# tractor.net
KiCad netlist of a schematic drawn in EAGLE
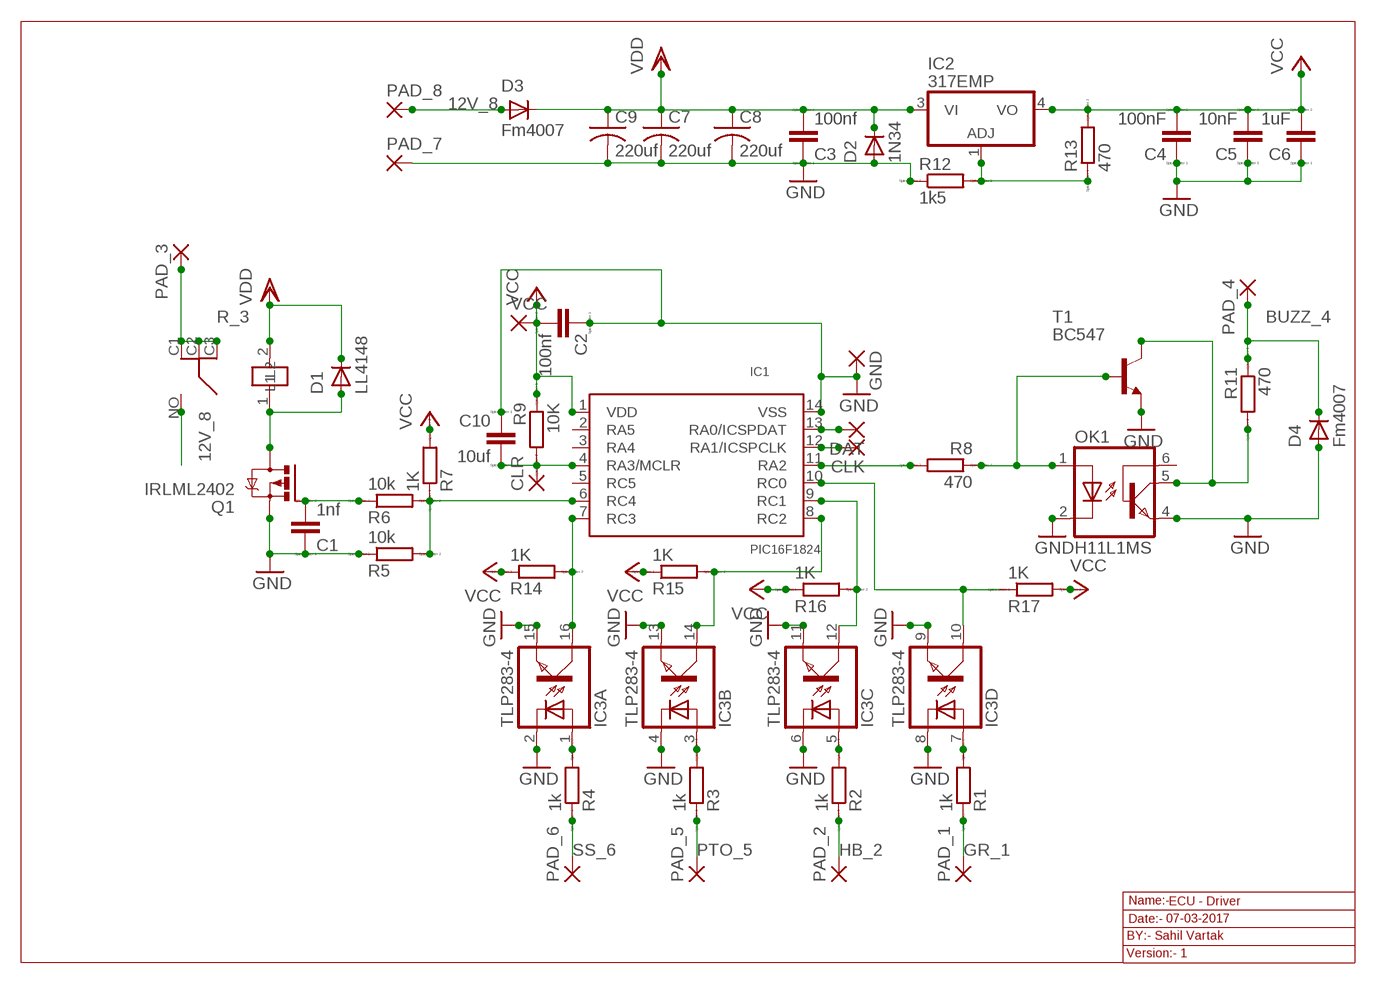
[diagram p0: schematic, sheet 1]

(export (version "E")
  (design (tool "Eeschema 10.0.6"))
  (components
    (comp (ref "C1")
      (value "1nf")
      (footprint "eagle-import:C0603")
      (libsource (lib "eagle-import") (part "CC0603"))
    )
    (comp (ref "C2")
      (value "100nf")
      (footprint "eagle-import:C0603")
      (libsource (lib "eagle-import") (part "CC0603"))
    )
    (comp (ref "C3")
      (value "100nf")
      (footprint "eagle-import:C0603")
      (libsource (lib "eagle-import") (part "CC0603"))
    )
    (comp (ref "C4")
      (value "100nF")
      (footprint "eagle-import:C0603")
      (libsource (lib "eagle-import") (part "CC0603"))
    )
    (comp (ref "C5")
      (value "10nF")
      (footprint "eagle-import:C0603")
      (libsource (lib "eagle-import") (part "CC0603"))
    )
    (comp (ref "C6")
      (value "1uF")
      (footprint "eagle-import:C0603")
      (libsource (lib "eagle-import") (part "CC0603"))
    )
    (comp (ref "C7")
      (value "220uf")
      (footprint "eagle-import:C025-025X050")
      (libsource (lib "eagle-import") (part "C-US025-025X050"))
    )
    (comp (ref "C8")
      (value "220uf")
      (footprint "eagle-import:C025-025X050")
      (libsource (lib "eagle-import") (part "C-US025-025X050"))
    )
    (comp (ref "C9")
      (value "220uf")
      (footprint "eagle-import:C025-025X050")
      (libsource (lib "eagle-import") (part "C-US025-025X050"))
    )
    (comp (ref "C10")
      (value "10uf")
      (footprint "eagle-import:C0603")
      (libsource (lib "eagle-import") (part "CC0603"))
    )
    (comp (ref "CLK")
      (value "1,6/0,8")
      (footprint "eagle-import:1,6_0,8")
      (libsource (lib "eagle-import") (part "1,6/0,8"))
    )
    (comp (ref "CLR")
      (value "1,6/0,8")
      (footprint "eagle-import:1,6_0,8")
      (libsource (lib "eagle-import") (part "1,6/0,8"))
    )
    (comp (ref "D1")
      (value "LL4148")
      (footprint "eagle-import:SMA-DO214AC")
      (libsource (lib "eagle-import") (part "GF1"))
    )
    (comp (ref "D2")
      (value "1N34")
      (footprint "eagle-import:SMA-DO214AC")
      (libsource (lib "eagle-import") (part "GF1"))
    )
    (comp (ref "D3")
      (value "Fm4007")
      (footprint "eagle-import:SMA-DO214AC")
      (libsource (lib "eagle-import") (part "GF1"))
    )
    (comp (ref "D4")
      (value "Fm4007")
      (footprint "eagle-import:SMA-DO214AC")
      (libsource (lib "eagle-import") (part "GF1"))
    )
    (comp (ref "DAT")
      (value "1,6/0,8")
      (footprint "eagle-import:1,6_0,8")
      (libsource (lib "eagle-import") (part "1,6/0,8"))
    )
    (comp (ref "GND")
      (value "1,6/0,8")
      (footprint "eagle-import:1,6_0,8")
      (libsource (lib "eagle-import") (part "1,6/0,8"))
    )
    (comp (ref "IC1")
      (value "PIC16F1824")
      (footprint "eagle-import:SO-14")
      (libsource (lib "eagle-import") (part "PIC16F1824"))
    )
    (comp (ref "IC2")
      (value "317EMP")
      (footprint "eagle-import:SOT223")
      (libsource (lib "eagle-import") (part "317EMP"))
    )
    (comp (ref "IC3")
      (value "TLP283-4")
      (footprint "eagle-import:MINI-FLAT-16")
      (libsource (lib "eagle-import") (part "TLP283-4"))
    )
    (comp (ref "K2")
      (value "RL703")
      (footprint "eagle-import:RL703")
      (libsource (lib "eagle-import") (part "RL703"))
    )
    (comp (ref "OK1")
      (value "H11L1MS")
      (footprint "eagle-import:DIL6-SMD")
      (libsource (lib "eagle-import") (part "H11LMS1"))
    )
    (comp (ref "PAD_1")
      (value "2,54/1,1")
      (footprint "eagle-import:2,54_1,1")
      (libsource (lib "eagle-import") (part "2,54/1,1"))
    )
    (comp (ref "PAD_2")
      (value "2,54/1,1")
      (footprint "eagle-import:2,54_1,1")
      (libsource (lib "eagle-import") (part "2,54/1,1"))
    )
    (comp (ref "PAD_3")
      (value "2,54/1,1")
      (footprint "eagle-import:2,54_1,1")
      (libsource (lib "eagle-import") (part "2,54/1,1"))
    )
    (comp (ref "PAD_4")
      (value "2,54/1,1")
      (footprint "eagle-import:2,54_1,1")
      (libsource (lib "eagle-import") (part "2,54/1,1"))
    )
    (comp (ref "PAD_5")
      (value "2,54/1,1")
      (footprint "eagle-import:2,54_1,1")
      (libsource (lib "eagle-import") (part "2,54/1,1"))
    )
    (comp (ref "PAD_6")
      (value "2,54/1,1")
      (footprint "eagle-import:2,54_1,1")
      (libsource (lib "eagle-import") (part "2,54/1,1"))
    )
    (comp (ref "PAD_7")
      (value "2,54/1,1")
      (footprint "eagle-import:2,54_1,1")
      (libsource (lib "eagle-import") (part "2,54/1,1"))
    )
    (comp (ref "PAD_8")
      (value "2,54/1,1")
      (footprint "eagle-import:2,54_1,1")
      (libsource (lib "eagle-import") (part "2,54/1,1"))
    )
    (comp (ref "Q1")
      (value "IRLML2402")
      (footprint "eagle-import:MICRO3")
      (libsource (lib "eagle-import") (part "IRLML5203"))
    )
    (comp (ref "R1")
      (value "1k")
      (footprint "eagle-import:R0603")
      (libsource (lib "eagle-import") (part "RR0603"))
    )
    (comp (ref "R2")
      (value "1k")
      (footprint "eagle-import:R0603")
      (libsource (lib "eagle-import") (part "RR0603"))
    )
    (comp (ref "R3")
      (value "1k")
      (footprint "eagle-import:R0603")
      (libsource (lib "eagle-import") (part "RR0603"))
    )
    (comp (ref "R4")
      (value "1k")
      (footprint "eagle-import:R0603")
      (libsource (lib "eagle-import") (part "RR0603"))
    )
    (comp (ref "R5")
      (value "10k")
      (footprint "eagle-import:R0603")
      (libsource (lib "eagle-import") (part "RR0603"))
    )
    (comp (ref "R6")
      (value "10k")
      (footprint "eagle-import:R0603")
      (libsource (lib "eagle-import") (part "RR0603"))
    )
    (comp (ref "R7")
      (value "1K")
      (footprint "eagle-import:R0603")
      (libsource (lib "eagle-import") (part "RR0603"))
    )
    (comp (ref "R8")
      (value "470")
      (footprint "eagle-import:R0603")
      (libsource (lib "eagle-import") (part "RR0603"))
    )
    (comp (ref "R9")
      (value "10K")
      (footprint "eagle-import:R0603")
      (libsource (lib "eagle-import") (part "RR0603"))
    )
    (comp (ref "R11")
      (value "470")
      (footprint "eagle-import:R0603")
      (libsource (lib "eagle-import") (part "RR0603"))
    )
    (comp (ref "R12")
      (value "1k5")
      (footprint "eagle-import:R0603")
      (libsource (lib "eagle-import") (part "RR0603"))
    )
    (comp (ref "R13")
      (value "470")
      (footprint "eagle-import:R0603")
      (libsource (lib "eagle-import") (part "RR0603"))
    )
    (comp (ref "R14")
      (value "1K")
      (footprint "eagle-import:R0603")
      (libsource (lib "eagle-import") (part "RR0603"))
    )
    (comp (ref "R15")
      (value "1K")
      (footprint "eagle-import:R0603")
      (libsource (lib "eagle-import") (part "RR0603"))
    )
    (comp (ref "R16")
      (value "1K")
      (footprint "eagle-import:R0603")
      (libsource (lib "eagle-import") (part "RR0603"))
    )
    (comp (ref "R17")
      (value "1K")
      (footprint "eagle-import:R0603")
      (libsource (lib "eagle-import") (part "RR0603"))
    )
    (comp (ref "T1")
      (value "BC547")
      (footprint "eagle-import:TO92")
      (libsource (lib "eagle-import") (part "BC547"))
    )
    (comp (ref "VCC")
      (value "1,6/0,8")
      (footprint "eagle-import:1,6_0,8")
      (libsource (lib "eagle-import") (part "1,6/0,8"))
    )
  )
  (nets
    (net (code "1") (name "/12V_8") (class "Default")
      (node (ref "D3") (pin "A") (pinfunction "A_A") (pintype "passive"))
      (node (ref "K2") (pin "NO") (pinfunction "NO_NO") (pintype "bidirectional"))
      (node (ref "PAD_8") (pin "1") (pinfunction "P_1") (pintype "passive"))
    )
    (net (code "2") (name "/BUZZ_4") (class "Default")
      (node (ref "D4") (pin "K") (pinfunction "C_K") (pintype "passive"))
      (node (ref "PAD_4") (pin "1") (pinfunction "P_1") (pintype "passive"))
      (node (ref "R11") (pin "1") (pinfunction "1_1") (pintype "passive"))
    )
    (net (code "3") (name "/GR_1") (class "Default")
      (node (ref "PAD_1") (pin "1") (pinfunction "P_1") (pintype "passive"))
      (node (ref "R1") (pin "1") (pinfunction "1_1") (pintype "passive"))
    )
    (net (code "4") (name "/HB_2") (class "Default")
      (node (ref "PAD_2") (pin "1") (pinfunction "P_1") (pintype "passive"))
      (node (ref "R2") (pin "1") (pinfunction "1_1") (pintype "passive"))
    )
    (net (code "5") (name "/PTO_5") (class "Default")
      (node (ref "PAD_5") (pin "1") (pinfunction "P_1") (pintype "passive"))
      (node (ref "R3") (pin "1") (pinfunction "1_1") (pintype "passive"))
    )
    (net (code "6") (name "/R_3") (class "Default")
      (node (ref "K2") (pin "C1") (pinfunction "C1_C1") (pintype "bidirectional"))
      (node (ref "K2") (pin "C2") (pinfunction "C2_C2") (pintype "bidirectional"))
      (node (ref "K2") (pin "C3") (pinfunction "C3_C3") (pintype "bidirectional"))
      (node (ref "PAD_3") (pin "1") (pinfunction "P_1") (pintype "passive"))
    )
    (net (code "7") (name "/SS_6") (class "Default")
      (node (ref "PAD_6") (pin "1") (pinfunction "P_1") (pintype "passive"))
      (node (ref "R4") (pin "1") (pinfunction "1_1") (pintype "passive"))
    )
    (net (code "8") (name "GND") (class "Default")
      (node (ref "C1") (pin "1") (pinfunction "1_1") (pintype "passive"))
      (node (ref "C10") (pin "1") (pinfunction "1_1") (pintype "passive"))
      (node (ref "C2") (pin "1") (pinfunction "1_1") (pintype "passive"))
      (node (ref "C3") (pin "1") (pinfunction "1_1") (pintype "passive"))
      (node (ref "C4") (pin "1") (pinfunction "1_1") (pintype "passive"))
      (node (ref "C5") (pin "1") (pinfunction "1_1") (pintype "passive"))
      (node (ref "C6") (pin "1") (pinfunction "1_1") (pintype "passive"))
      (node (ref "C7") (pin "2") (pinfunction "2_2") (pintype "passive"))
      (node (ref "C8") (pin "2") (pinfunction "2_2") (pintype "passive"))
      (node (ref "C9") (pin "2") (pinfunction "2_2") (pintype "passive"))
      (node (ref "D2") (pin "A") (pinfunction "A_A") (pintype "passive"))
      (node (ref "D4") (pin "A") (pinfunction "A_A") (pintype "passive"))
      (node (ref "GND") (pin "1") (pinfunction "P_1") (pintype "passive"))
      (node (ref "IC1") (pin "14") (pinfunction "VSS_14") (pintype "bidirectional"))
      (node (ref "IC3") (pin "11") (pinfunction "EMIT_11") (pintype "passive"))
      (node (ref "IC3") (pin "13") (pinfunction "EMIT_13") (pintype "passive"))
      (node (ref "IC3") (pin "15") (pinfunction "EMIT_15") (pintype "passive"))
      (node (ref "IC3") (pin "2") (pinfunction "C_2") (pintype "passive"))
      (node (ref "IC3") (pin "4") (pinfunction "C_4") (pintype "passive"))
      (node (ref "IC3") (pin "6") (pinfunction "C_6") (pintype "passive"))
      (node (ref "IC3") (pin "8") (pinfunction "C_8") (pintype "passive"))
      (node (ref "IC3") (pin "9") (pinfunction "EMIT_9") (pintype "passive"))
      (node (ref "OK1") (pin "2") (pinfunction "C_2") (pintype "passive"))
      (node (ref "OK1") (pin "4") (pinfunction "EMI_4") (pintype "passive"))
      (node (ref "PAD_7") (pin "1") (pinfunction "P_1") (pintype "passive"))
      (node (ref "Q1") (pin "2") (pinfunction "S_2") (pintype "passive"))
      (node (ref "R12") (pin "1") (pinfunction "1_1") (pintype "passive"))
      (node (ref "R5") (pin "1") (pinfunction "1_1") (pintype "passive"))
      (node (ref "T1") (pin "1") (pinfunction "E_1") (pintype "passive"))
    )
    (net (code "9") (name "Net-(CLK-P)") (class "Default")
      (node (ref "CLK") (pin "1") (pinfunction "P_1") (pintype "passive"))
      (node (ref "IC1") (pin "12") (pinfunction "RA1/ICSPCLK_12") (pintype "bidirectional"))
    )
    (net (code "10") (name "Net-(CLR-P)") (class "Default")
      (node (ref "C10") (pin "2") (pinfunction "2_2") (pintype "passive"))
      (node (ref "CLR") (pin "1") (pinfunction "P_1") (pintype "passive"))
      (node (ref "IC1") (pin "4") (pinfunction "RA3/MCLR_4") (pintype "bidirectional"))
      (node (ref "R9") (pin "2") (pinfunction "2_2") (pintype "passive"))
    )
    (net (code "11") (name "Net-(DAT-P)") (class "Default")
      (node (ref "DAT") (pin "1") (pinfunction "P_1") (pintype "passive"))
      (node (ref "IC1") (pin "13") (pinfunction "RA0/ICSPDAT_13") (pintype "bidirectional"))
    )
    (net (code "12") (name "Net-(IC1-RA2)") (class "Default")
      (node (ref "IC1") (pin "11") (pinfunction "RA2_11") (pintype "bidirectional"))
      (node (ref "R8") (pin "2") (pinfunction "2_2") (pintype "passive"))
    )
    (net (code "13") (name "Net-(IC1-RC0)") (class "Default")
      (node (ref "IC1") (pin "10") (pinfunction "RC0_10") (pintype "bidirectional"))
      (node (ref "IC3") (pin "10") (pinfunction "COL_10") (pintype "passive"))
      (node (ref "R17") (pin "1") (pinfunction "1_1") (pintype "passive"))
    )
    (net (code "14") (name "Net-(IC1-RC1)") (class "Default")
      (node (ref "IC1") (pin "9") (pinfunction "RC1_9") (pintype "bidirectional"))
      (node (ref "IC3") (pin "12") (pinfunction "COL_12") (pintype "passive"))
      (node (ref "R16") (pin "2") (pinfunction "2_2") (pintype "passive"))
    )
    (net (code "15") (name "Net-(IC1-RC2)") (class "Default")
      (node (ref "IC1") (pin "8") (pinfunction "RC2_8") (pintype "bidirectional"))
      (node (ref "IC3") (pin "14") (pinfunction "COL_14") (pintype "passive"))
      (node (ref "R15") (pin "2") (pinfunction "2_2") (pintype "passive"))
    )
    (net (code "16") (name "Net-(IC1-RC3)") (class "Default")
      (node (ref "IC1") (pin "7") (pinfunction "RC3_7") (pintype "bidirectional"))
      (node (ref "IC3") (pin "16") (pinfunction "COL_16") (pintype "passive"))
      (node (ref "R14") (pin "2") (pinfunction "2_2") (pintype "passive"))
    )
    (net (code "17") (name "Net-(IC1-RC4)") (class "Default")
      (node (ref "IC1") (pin "6") (pinfunction "RC4_6") (pintype "bidirectional"))
      (node (ref "R5") (pin "2") (pinfunction "2_2") (pintype "passive"))
      (node (ref "R6") (pin "2") (pinfunction "2_2") (pintype "passive"))
      (node (ref "R7") (pin "1") (pinfunction "1_1") (pintype "passive"))
    )
    (net (code "18") (name "Net-(IC2-ADJ)") (class "Default")
      (node (ref "IC2") (pin "1") (pinfunction "ADJ_1") (pintype "input"))
      (node (ref "R12") (pin "2") (pinfunction "2_2") (pintype "passive"))
      (node (ref "R13") (pin "1") (pinfunction "1_1") (pintype "passive"))
    )
    (net (code "19") (name "Net-(IC3A-A)") (class "Default")
      (node (ref "IC3") (pin "1") (pinfunction "A_1") (pintype "passive"))
      (node (ref "R4") (pin "2") (pinfunction "2_2") (pintype "passive"))
    )
    (net (code "20") (name "Net-(IC3B-A)") (class "Default")
      (node (ref "IC3") (pin "3") (pinfunction "A_3") (pintype "passive"))
      (node (ref "R3") (pin "2") (pinfunction "2_2") (pintype "passive"))
    )
    (net (code "21") (name "Net-(IC3C-A)") (class "Default")
      (node (ref "IC3") (pin "5") (pinfunction "A_5") (pintype "passive"))
      (node (ref "R2") (pin "2") (pinfunction "2_2") (pintype "passive"))
    )
    (net (code "22") (name "Net-(IC3D-A)") (class "Default")
      (node (ref "IC3") (pin "7") (pinfunction "A_7") (pintype "passive"))
      (node (ref "R1") (pin "2") (pinfunction "2_2") (pintype "passive"))
    )
    (net (code "23") (name "Net-(K2-L2)") (class "Default")
      (node (ref "D1") (pin "A") (pinfunction "A_A") (pintype "passive"))
      (node (ref "K2") (pin "1") (pinfunction "L2_1") (pintype "bidirectional"))
      (node (ref "Q1") (pin "3") (pinfunction "D_3") (pintype "passive"))
    )
    (net (code "24") (name "Net-(OK1-A)") (class "Default")
      (node (ref "OK1") (pin "1") (pinfunction "A_1") (pintype "passive"))
      (node (ref "R8") (pin "1") (pinfunction "1_1") (pintype "passive"))
      (node (ref "T1") (pin "2") (pinfunction "B_2") (pintype "passive"))
    )
    (net (code "25") (name "Net-(OK1-COL)") (class "Default")
      (node (ref "OK1") (pin "5") (pinfunction "COL_5") (pintype "passive"))
      (node (ref "R11") (pin "2") (pinfunction "2_2") (pintype "passive"))
      (node (ref "T1") (pin "3") (pinfunction "C_3") (pintype "passive"))
    )
    (net (code "26") (name "Net-(Q1-G)") (class "Default")
      (node (ref "C1") (pin "2") (pinfunction "2_2") (pintype "passive"))
      (node (ref "Q1") (pin "1") (pinfunction "G_1") (pintype "passive"))
      (node (ref "R6") (pin "1") (pinfunction "1_1") (pintype "passive"))
    )
    (net (code "27") (name "VCC") (class "Default")
      (node (ref "C2") (pin "2") (pinfunction "2_2") (pintype "passive"))
      (node (ref "C4") (pin "2") (pinfunction "2_2") (pintype "passive"))
      (node (ref "C5") (pin "2") (pinfunction "2_2") (pintype "passive"))
      (node (ref "C6") (pin "2") (pinfunction "2_2") (pintype "passive"))
      (node (ref "IC1") (pin "1") (pinfunction "VDD_1") (pintype "bidirectional"))
      (node (ref "IC2") (pin "4") (pinfunction "VO_4") (pintype "passive"))
      (node (ref "R13") (pin "2") (pinfunction "2_2") (pintype "passive"))
      (node (ref "R14") (pin "1") (pinfunction "1_1") (pintype "passive"))
      (node (ref "R15") (pin "1") (pinfunction "1_1") (pintype "passive"))
      (node (ref "R16") (pin "1") (pinfunction "1_1") (pintype "passive"))
      (node (ref "R17") (pin "2") (pinfunction "2_2") (pintype "passive"))
      (node (ref "R7") (pin "2") (pinfunction "2_2") (pintype "passive"))
      (node (ref "R9") (pin "1") (pinfunction "1_1") (pintype "passive"))
      (node (ref "VCC") (pin "1") (pinfunction "P_1") (pintype "passive"))
    )
    (net (code "28") (name "VDD") (class "Default")
      (node (ref "C3") (pin "2") (pinfunction "2_2") (pintype "passive"))
      (node (ref "C7") (pin "1") (pinfunction "1_1") (pintype "passive"))
      (node (ref "C8") (pin "1") (pinfunction "1_1") (pintype "passive"))
      (node (ref "C9") (pin "1") (pinfunction "1_1") (pintype "passive"))
      (node (ref "D1") (pin "K") (pinfunction "C_K") (pintype "passive"))
      (node (ref "D2") (pin "K") (pinfunction "C_K") (pintype "passive"))
      (node (ref "D3") (pin "K") (pinfunction "C_K") (pintype "passive"))
      (node (ref "IC2") (pin "3") (pinfunction "VI_3") (pintype "input"))
      (node (ref "K2") (pin "2") (pinfunction "L1_2") (pintype "bidirectional"))
    )
    (net (code "29") (name "unconnected-(IC1-RA4-Pad3)") (class "Default")
      (node (ref "IC1") (pin "3") (pinfunction "RA4_3") (pintype "bidirectional"))
    )
    (net (code "30") (name "unconnected-(IC1-RA5-Pad2)") (class "Default")
      (node (ref "IC1") (pin "2") (pinfunction "RA5_2") (pintype "bidirectional"))
    )
    (net (code "31") (name "unconnected-(IC1-RC5-Pad5)") (class "Default")
      (node (ref "IC1") (pin "5") (pinfunction "RC5_5") (pintype "bidirectional"))
    )
    (net (code "32") (name "unconnected-(OK1-BAS-Pad6)") (class "Default")
      (node (ref "OK1") (pin "6") (pinfunction "BAS_6") (pintype "passive"))
    )
  )
)
